# 4_Led_Output.net
KiCad netlist of a schematic drawn in Altium Designer
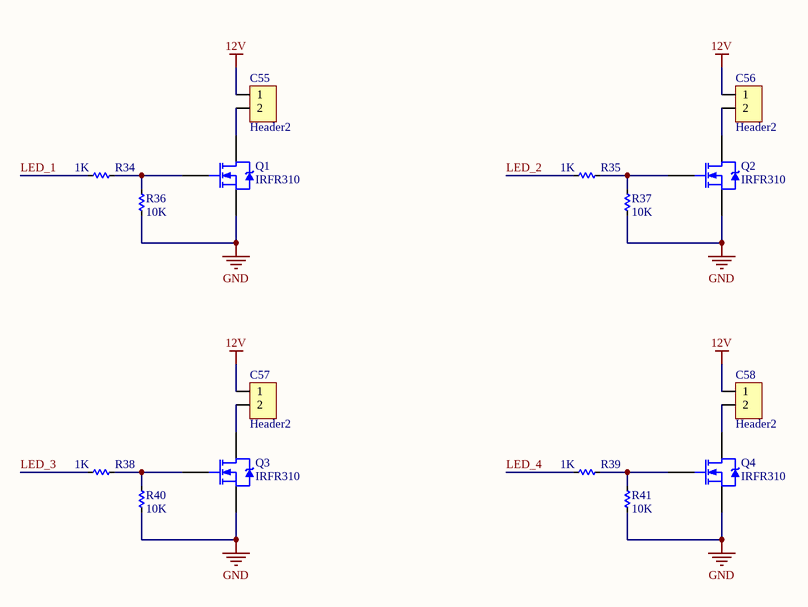
[diagram p0: [4]Led_Output.SchDoc]

(export (version "E")
  (design (tool "Eeschema 10.0.6"))
  (components
    (comp (ref "C55")
      (value "Header2")
      (footprint "Header2")
      (description "Header IDC, 2 x 1 Pin Vertical 2.54mm Pitch (Non-Boxed, Male)")
      (fields
        (field (name "MANUFACTURER") "Würth Elektronik eiSos GmbH")
        (field (name "PARTNO") "613002143121")
        (field (name "CREATED BY") "Karrer Zheng")
      )
      (libsource (lib "LIBRARY") (part "Header2"))
    )
    (comp (ref "C56")
      (value "Header2")
      (footprint "Header2")
      (description "Header IDC, 2 x 1 Pin Vertical 2.54mm Pitch (Non-Boxed, Male)")
      (fields
        (field (name "MANUFACTURER") "Würth Elektronik eiSos GmbH")
        (field (name "PARTNO") "613002143121")
        (field (name "CREATED BY") "Karrer Zheng")
      )
      (libsource (lib "LIBRARY") (part "Header2"))
    )
    (comp (ref "C57")
      (value "Header2")
      (footprint "Header2")
      (description "Header IDC, 2 x 1 Pin Vertical 2.54mm Pitch (Non-Boxed, Male)")
      (fields
        (field (name "MANUFACTURER") "Würth Elektronik eiSos GmbH")
        (field (name "PARTNO") "613002143121")
        (field (name "CREATED BY") "Karrer Zheng")
      )
      (libsource (lib "LIBRARY") (part "Header2"))
    )
    (comp (ref "C58")
      (value "Header2")
      (footprint "Header2")
      (description "Header IDC, 2 x 1 Pin Vertical 2.54mm Pitch (Non-Boxed, Male)")
      (fields
        (field (name "MANUFACTURER") "Würth Elektronik eiSos GmbH")
        (field (name "PARTNO") "613002143121")
        (field (name "CREATED BY") "Karrer Zheng")
      )
      (libsource (lib "LIBRARY") (part "Header2"))
    )
    (comp (ref "Q1")
      (value "IRFR310")
      (footprint "TO-252AA_N")
      (description "HEXFET Power MOSFET")
      (fields (field (name "PUBLISHER") "Altium Limited"))
      (libsource (lib "IR Discrete MOSFET - Power") (part "IRFR310"))
    )
    (comp (ref "Q2")
      (value "IRFR310")
      (footprint "TO-252AA_N")
      (description "HEXFET Power MOSFET")
      (fields (field (name "PUBLISHER") "Altium Limited"))
      (libsource (lib "IR Discrete MOSFET - Power") (part "IRFR310"))
    )
    (comp (ref "Q3")
      (value "IRFR310")
      (footprint "TO-252AA_N")
      (description "HEXFET Power MOSFET")
      (fields (field (name "PUBLISHER") "Altium Limited"))
      (libsource (lib "IR Discrete MOSFET - Power") (part "IRFR310"))
    )
    (comp (ref "Q4")
      (value "IRFR310")
      (footprint "TO-252AA_N")
      (description "HEXFET Power MOSFET")
      (fields (field (name "PUBLISHER") "Altium Limited"))
      (libsource (lib "IR Discrete MOSFET - Power") (part "IRFR310"))
    )
    (comp (ref "R34")
      (value "1K")
      (footprint "RES-SMD-0603")
      (description "Resistor")
      (fields
        (field (name "MANUFACTURER") "Generic Components")
        (field (name "PUBLISHER") "Altium Hobart Technology Centre")
      )
      (libsource (lib "LIBRARY") (part "Res-SMD"))
    )
    (comp (ref "R35")
      (value "1K")
      (footprint "RES-SMD-0603")
      (description "Resistor")
      (fields
        (field (name "MANUFACTURER") "Generic Components")
        (field (name "PUBLISHER") "Altium Hobart Technology Centre")
      )
      (libsource (lib "LIBRARY") (part "Res-SMD"))
    )
    (comp (ref "R36")
      (value "10K")
      (footprint "RES-SMD-0603")
      (description "Resistor")
      (fields
        (field (name "MANUFACTURER") "Generic Components")
        (field (name "PUBLISHER") "Altium Hobart Technology Centre")
      )
      (libsource (lib "LIBRARY") (part "Res-SMD"))
    )
    (comp (ref "R37")
      (value "10K")
      (footprint "RES-SMD-0603")
      (description "Resistor")
      (fields
        (field (name "MANUFACTURER") "Generic Components")
        (field (name "PUBLISHER") "Altium Hobart Technology Centre")
      )
      (libsource (lib "LIBRARY") (part "Res-SMD"))
    )
    (comp (ref "R38")
      (value "1K")
      (footprint "RES-SMD-0603")
      (description "Resistor")
      (fields
        (field (name "MANUFACTURER") "Generic Components")
        (field (name "PUBLISHER") "Altium Hobart Technology Centre")
      )
      (libsource (lib "LIBRARY") (part "Res-SMD"))
    )
    (comp (ref "R39")
      (value "1K")
      (footprint "RES-SMD-0603")
      (description "Resistor")
      (fields
        (field (name "MANUFACTURER") "Generic Components")
        (field (name "PUBLISHER") "Altium Hobart Technology Centre")
      )
      (libsource (lib "LIBRARY") (part "Res-SMD"))
    )
    (comp (ref "R40")
      (value "10K")
      (footprint "RES-SMD-0603")
      (description "Resistor")
      (fields
        (field (name "MANUFACTURER") "Generic Components")
        (field (name "PUBLISHER") "Altium Hobart Technology Centre")
      )
      (libsource (lib "LIBRARY") (part "Res-SMD"))
    )
    (comp (ref "R41")
      (value "10K")
      (footprint "RES-SMD-0603")
      (description "Resistor")
      (fields
        (field (name "MANUFACTURER") "Generic Components")
        (field (name "PUBLISHER") "Altium Hobart Technology Centre")
      )
      (libsource (lib "LIBRARY") (part "Res-SMD"))
    )
  )
  (nets
    (net (code "1") (name "/LED_1") (class "Default")
      (node (ref "R34") (pin "2") (pinfunction "2_2") (pintype "passive"))
    )
    (net (code "2") (name "/LED_2") (class "Default")
      (node (ref "R35") (pin "2") (pinfunction "2_2") (pintype "passive"))
    )
    (net (code "3") (name "/LED_3") (class "Default")
      (node (ref "R38") (pin "2") (pinfunction "2_2") (pintype "passive"))
    )
    (net (code "4") (name "/LED_4") (class "Default")
      (node (ref "R39") (pin "2") (pinfunction "2_2") (pintype "passive"))
    )
    (net (code "5") (name "12V") (class "Default")
      (node (ref "C55") (pin "1") (pinfunction "1_1") (pintype "passive"))
      (node (ref "C56") (pin "1") (pinfunction "1_1") (pintype "passive"))
      (node (ref "C57") (pin "1") (pinfunction "1_1") (pintype "passive"))
      (node (ref "C58") (pin "1") (pinfunction "1_1") (pintype "passive"))
    )
    (net (code "6") (name "GND") (class "Default")
      (node (ref "Q1") (pin "3") (pinfunction "S_3") (pintype "passive"))
      (node (ref "Q2") (pin "3") (pinfunction "S_3") (pintype "passive"))
      (node (ref "Q3") (pin "3") (pinfunction "S_3") (pintype "passive"))
      (node (ref "Q4") (pin "3") (pinfunction "S_3") (pintype "passive"))
      (node (ref "R36") (pin "2") (pinfunction "2_2") (pintype "passive"))
      (node (ref "R37") (pin "2") (pinfunction "2_2") (pintype "passive"))
      (node (ref "R40") (pin "2") (pinfunction "2_2") (pintype "passive"))
      (node (ref "R41") (pin "2") (pinfunction "2_2") (pintype "passive"))
    )
    (net (code "7") (name "Net-(Q1-D)") (class "Default")
      (node (ref "C55") (pin "2") (pinfunction "2_2") (pintype "passive"))
      (node (ref "Q1") (pin "4") (pinfunction "D_4") (pintype "passive"))
    )
    (net (code "8") (name "Net-(Q1-G)") (class "Default")
      (node (ref "Q1") (pin "1") (pinfunction "G_1") (pintype "passive"))
      (node (ref "R34") (pin "1") (pinfunction "1_1") (pintype "passive"))
      (node (ref "R36") (pin "1") (pinfunction "1_1") (pintype "passive"))
    )
    (net (code "9") (name "Net-(Q2-D)") (class "Default")
      (node (ref "C56") (pin "2") (pinfunction "2_2") (pintype "passive"))
      (node (ref "Q2") (pin "4") (pinfunction "D_4") (pintype "passive"))
    )
    (net (code "10") (name "Net-(Q2-G)") (class "Default")
      (node (ref "Q2") (pin "1") (pinfunction "G_1") (pintype "passive"))
      (node (ref "R35") (pin "1") (pinfunction "1_1") (pintype "passive"))
      (node (ref "R37") (pin "1") (pinfunction "1_1") (pintype "passive"))
    )
    (net (code "11") (name "Net-(Q3-D)") (class "Default")
      (node (ref "C57") (pin "2") (pinfunction "2_2") (pintype "passive"))
      (node (ref "Q3") (pin "4") (pinfunction "D_4") (pintype "passive"))
    )
    (net (code "12") (name "Net-(Q3-G)") (class "Default")
      (node (ref "Q3") (pin "1") (pinfunction "G_1") (pintype "passive"))
      (node (ref "R38") (pin "1") (pinfunction "1_1") (pintype "passive"))
      (node (ref "R40") (pin "1") (pinfunction "1_1") (pintype "passive"))
    )
    (net (code "13") (name "Net-(Q4-D)") (class "Default")
      (node (ref "C58") (pin "2") (pinfunction "2_2") (pintype "passive"))
      (node (ref "Q4") (pin "4") (pinfunction "D_4") (pintype "passive"))
    )
    (net (code "14") (name "Net-(Q4-G)") (class "Default")
      (node (ref "Q4") (pin "1") (pinfunction "G_1") (pintype "passive"))
      (node (ref "R39") (pin "1") (pinfunction "1_1") (pintype "passive"))
      (node (ref "R41") (pin "1") (pinfunction "1_1") (pintype "passive"))
    )
  )
)
